# PhatStats_Slim_Enclosure_ESP_Lolin32_LIT.net
KiCad netlist of a schematic drawn in EAGLE
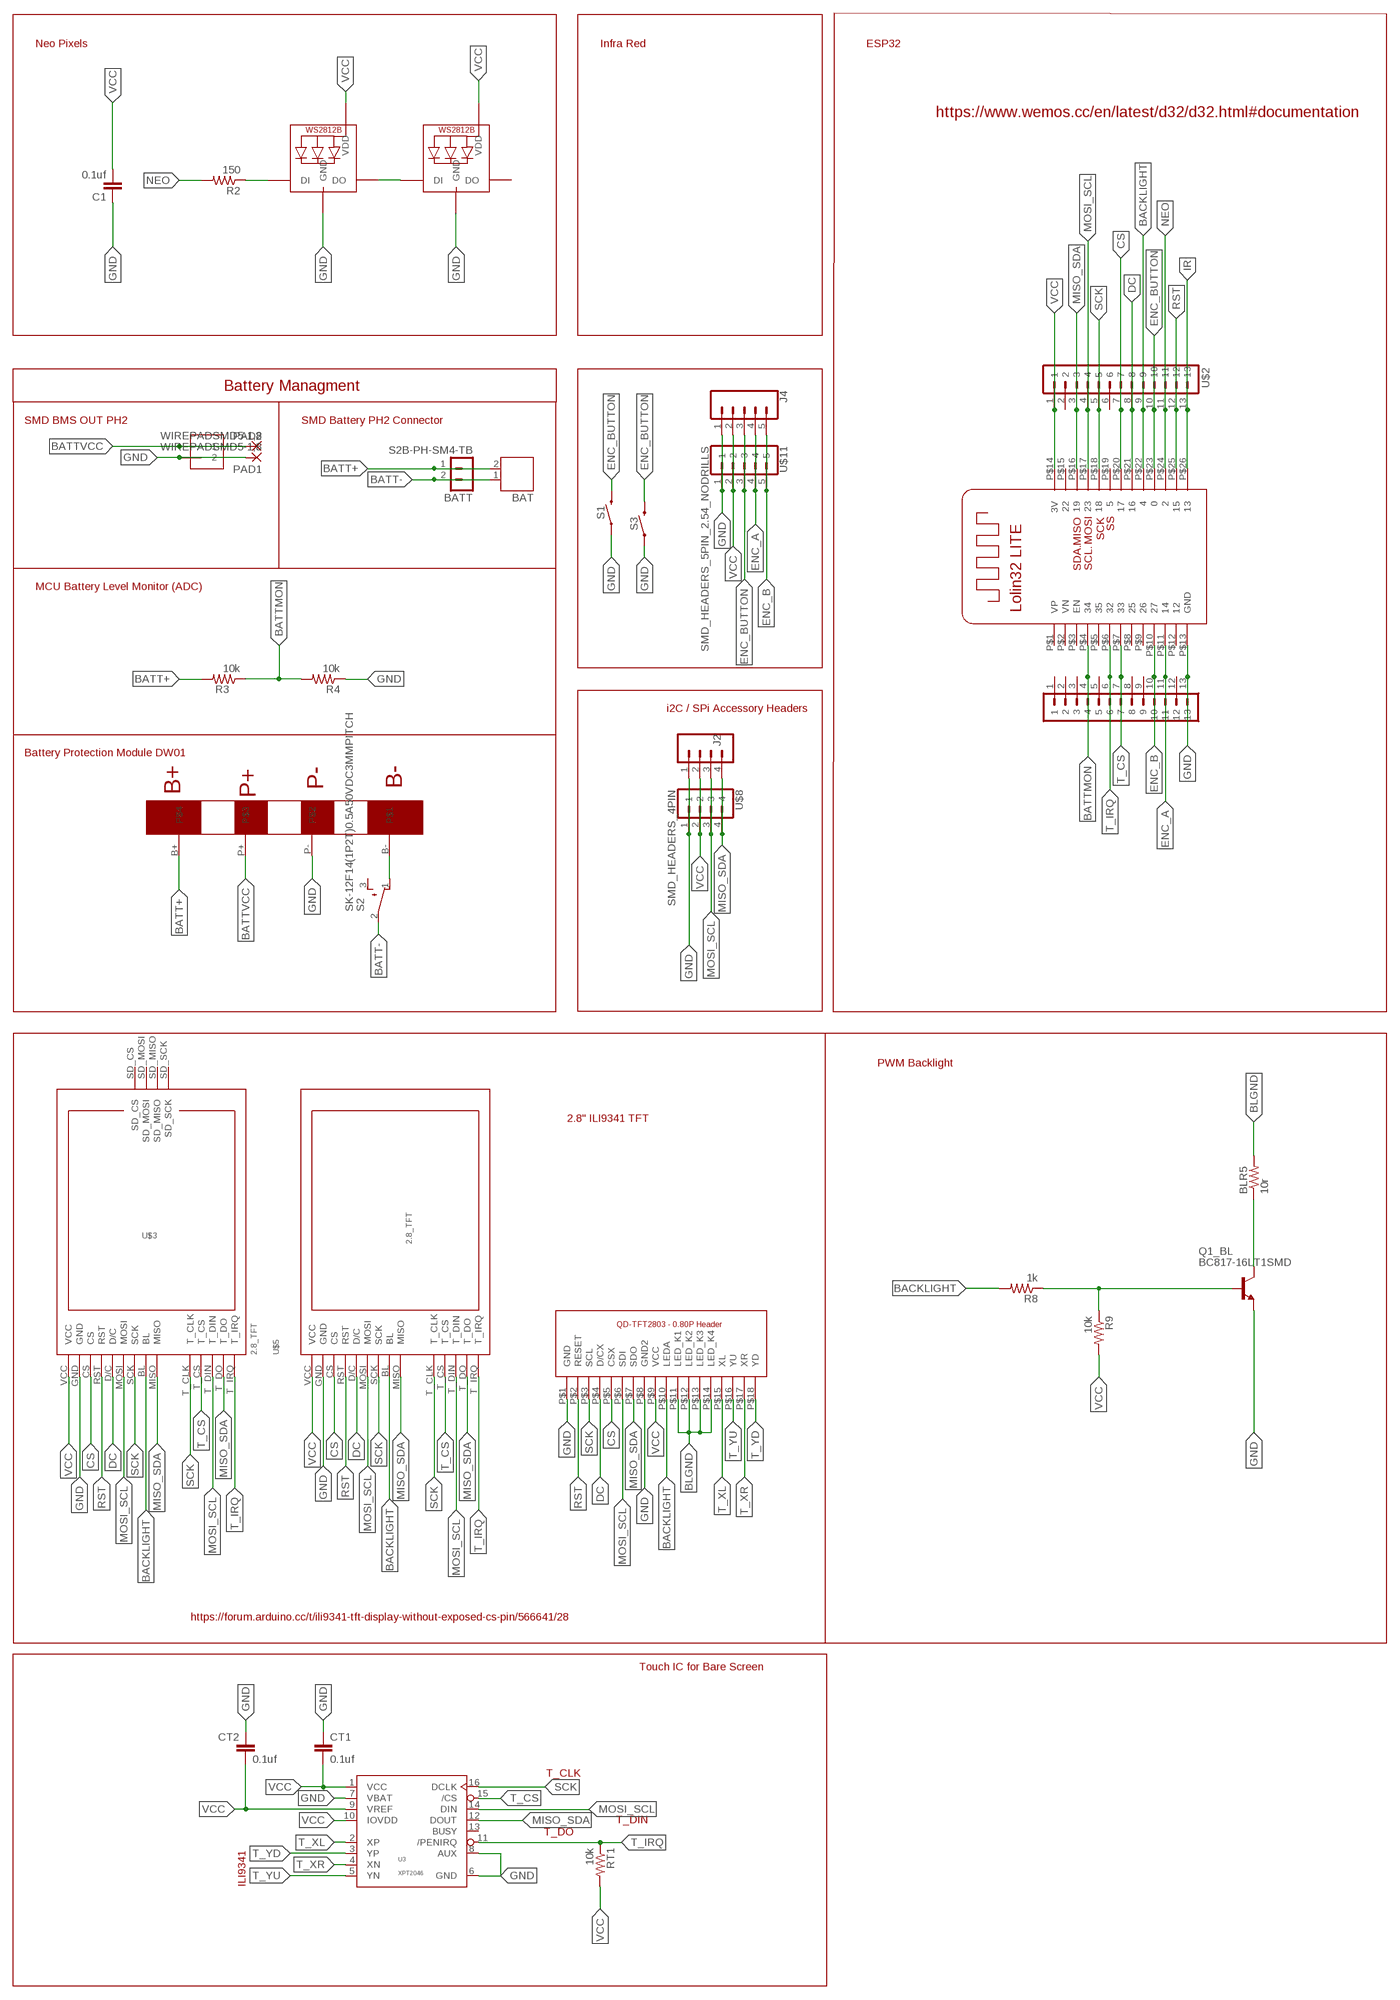
[diagram p0: schematic, sheet 1]

(export (version "E")
  (design (tool "Eeschema 10.0.6"))
  (components
    (comp (ref "0")
      (value "ILI9341-2.8")
      (footprint "eagle-import:ILI9341-2.8")
      (libsource (lib "eagle-import") (part "ILI9341-2.8"))
    )
    (comp (ref "BAT")
      (value "JST-PH2")
      (footprint "eagle-import:JST-PH2")
      (libsource (lib "eagle-import") (part "JST-PH2"))
    )
    (comp (ref "BATT")
      (value "S2B-PH-SM4-TB")
      (footprint "eagle-import:S2B-PH-SM4-TB")
      (libsource (lib "eagle-import") (part "S2B-PH-SM4-TB"))
    )
    (comp (ref "BLR5")
      (value "10r")
      (footprint "eagle-import:M1206")
      (libsource (lib "eagle-import") (part "R-US_M1206"))
    )
    (comp (ref "C1")
      (value "0.1uf")
      (footprint "eagle-import:C1206")
      (libsource (lib "eagle-import") (part "C-EUC1206"))
    )
    (comp (ref "CT1")
      (value "0.1uf")
      (footprint "eagle-import:C1206")
      (libsource (lib "eagle-import") (part "C-EUC1206"))
    )
    (comp (ref "CT2")
      (value "0.1uf")
      (footprint "eagle-import:C1206")
      (libsource (lib "eagle-import") (part "C-EUC1206"))
    )
    (comp (ref "DW01-BMS")
      (value "DW01BATTERYPROT")
      (footprint "eagle-import:DW01BATTERYPROT")
      (libsource (lib "eagle-import") (part "DW01BATTERYPROT"))
    )
    (comp (ref "J1")
      (value "1X2-3.5MM")
      (footprint "eagle-import:1X2-3.5MM")
      (libsource (lib "eagle-import") (part "1X2-3.5MM"))
    )
    (comp (ref "J2")
      (value "CONN_04PTH")
      (footprint "eagle-import:1X04")
      (libsource (lib "eagle-import") (part "CONN_04PTH"))
    )
    (comp (ref "J4")
      (value "CONN_05")
      (footprint "eagle-import:1X05")
      (libsource (lib "eagle-import") (part "CONN_05"))
    )
    (comp (ref "NEO1")
      (value "WS2812B5050")
      (footprint "eagle-import:WS2812B")
      (libsource (lib "eagle-import") (part "WS2812B5050"))
    )
    (comp (ref "NEO2")
      (value "WS2812B5050")
      (footprint "eagle-import:WS2812B")
      (libsource (lib "eagle-import") (part "WS2812B5050"))
    )
    (comp (ref "PAD1")
      (value "WIREPADSMD5-1,8")
      (footprint "eagle-import:5-1,8")
      (libsource (lib "eagle-import") (part "WIREPADSMD5-1,8"))
    )
    (comp (ref "PAD2")
      (value "WIREPADSMD5-1,8")
      (footprint "eagle-import:5-1,8")
      (libsource (lib "eagle-import") (part "WIREPADSMD5-1,8"))
    )
    (comp (ref "Q1_BL")
      (value "BC817-16LT1SMD")
      (footprint "eagle-import:SOT23-BEC")
      (libsource (lib "eagle-import") (part "BC817SMD-16LT1"))
    )
    (comp (ref "R2")
      (value "150")
      (footprint "eagle-import:M1206")
      (libsource (lib "eagle-import") (part "R-US_M1206"))
    )
    (comp (ref "R3")
      (value "10k")
      (footprint "eagle-import:M1206")
      (libsource (lib "eagle-import") (part "R-US_M1206"))
    )
    (comp (ref "R4")
      (value "10k")
      (footprint "eagle-import:M1206")
      (libsource (lib "eagle-import") (part "R-US_M1206"))
    )
    (comp (ref "R8")
      (value "1k")
      (footprint "eagle-import:M1206")
      (libsource (lib "eagle-import") (part "R-US_M1206"))
    )
    (comp (ref "R9")
      (value "10k")
      (footprint "eagle-import:M1206")
      (libsource (lib "eagle-import") (part "R-US_M1206"))
    )
    (comp (ref "RT1")
      (value "10k")
      (footprint "eagle-import:M1206")
      (libsource (lib "eagle-import") (part "R-US_M1206"))
    )
    (comp (ref "S1")
      (value "MOMENTARY-SWITCH-SPST-PTH-6.0MM")
      (footprint "eagle-import:TACTILE_SWITCH_PTH_6.0MM")
      (libsource (lib "eagle-import") (part "MOMENTARY-SWITCH-SPST-PTH-6.0MM"))
    )
    (comp (ref "S2")
      (value "SK-12F14(1P2T)0.5A50VDC3MMPITCH")
      (footprint "eagle-import:SK-12F14(1P2T)0.5A50VDC3MMPITCH")
      (libsource (lib "eagle-import") (part "SK-12F14(1P2T)0.5A50VDC3MMPITCH"))
    )
    (comp (ref "S3")
      (value "MOMENTARY-SWITCH-SPST-SMD-6.2MM-TALL")
      (footprint "eagle-import:TACTILE_SWITCH_SMD_6.2MM_TALL")
      (libsource (lib "eagle-import") (part "MOMENTARY-SWITCH-SPST-SMD-6.2MM-TALL"))
    )
    (comp (ref "U$1")
      (value "SMD_HEADERS_13PIN_2.54_NODRILLS")
      (footprint "eagle-import:SMD_HEADERS_13PIN")
      (libsource (lib "eagle-import") (part "SMD_HEADERS_13PIN_2.54_NODRILLS"))
    )
    (comp (ref "U$2")
      (value "SMD_HEADERS_13PIN_2.54_NODRILLS")
      (footprint "eagle-import:SMD_HEADERS_13PIN")
      (libsource (lib "eagle-import") (part "SMD_HEADERS_13PIN_2.54_NODRILLS"))
    )
    (comp (ref "U$3")
      (value "2.8_TFT")
      (footprint "eagle-import:2.8_TFT")
      (libsource (lib "eagle-import") (part "2.8_TFT"))
    )
    (comp (ref "U$5")
      (value "2.8_TFT")
      (footprint "eagle-import:2.8_TFT")
      (libsource (lib "eagle-import") (part "TML_ili9341-2.8_tft-display_PinHeader only_2.8_TFT"))
    )
    (comp (ref "U$7")
      (value "TML_LOLIND32_LITE")
      (footprint "eagle-import:TML_LOLIND32_LITE")
      (libsource (lib "eagle-import") (part "TML_LOLIND32_LITE"))
    )
    (comp (ref "U$8")
      (value "SMD_HEADERS_4PIN")
      (footprint "eagle-import:SMD_HEADERS_4PIN")
      (libsource (lib "eagle-import") (part "SMD_HEADERS_4PIN"))
    )
    (comp (ref "U$11")
      (value "SMD_HEADERS_5PIN_2.54_NODRILLS")
      (footprint "eagle-import:SMD_HEADERS_5PIN")
      (libsource (lib "eagle-import") (part "SMD_HEADERS_5PIN_2.54_NODRILLS"))
    )
    (comp (ref "U3")
      (value "XPT2046")
      (footprint "eagle-import:TSSOP-16")
      (fields (field (name "MF") "Xptek"))
      (libsource (lib "eagle-import") (part "XPT2046"))
    )
  )
  (nets
    (net (code "1") (name "BACKLIGHT") (class "Default")
      (node (ref "0") (pin "P$10") (pinfunction "LEDA_P$10") (pintype "bidirectional"))
      (node (ref "R8") (pin "2") (pinfunction "2_2") (pintype "passive"))
      (node (ref "U$2") (pin "9") (pinfunction "9_9") (pintype "bidirectional"))
      (node (ref "U$3") (pin "BL") (pinfunction "BL_BL") (pintype "bidirectional"))
      (node (ref "U$5") (pin "BL") (pinfunction "BL_BL") (pintype "bidirectional"))
      (node (ref "U$7") (pin "P$22") (pinfunction "4_P$22") (pintype "bidirectional"))
    )
    (net (code "2") (name "BATT+") (class "Default")
      (node (ref "BAT") (pin "2") (pinfunction "2_2") (pintype "passive"))
      (node (ref "BATT") (pin "1") (pinfunction "1_1") (pintype "passive"))
      (node (ref "DW01-BMS") (pin "B+") (pinfunction "P$4_B+") (pintype "bidirectional"))
      (node (ref "R3") (pin "2") (pinfunction "2_2") (pintype "passive"))
    )
    (net (code "3") (name "BATT-") (class "Default")
      (node (ref "BAT") (pin "1") (pinfunction "1_1") (pintype "passive"))
      (node (ref "BATT") (pin "2") (pinfunction "2_2") (pintype "passive"))
      (node (ref "S2") (pin "2") (pinfunction "P_2") (pintype "passive"))
    )
    (net (code "4") (name "BATTMON") (class "Default")
      (node (ref "R3") (pin "1") (pinfunction "1_1") (pintype "passive"))
      (node (ref "R4") (pin "2") (pinfunction "2_2") (pintype "passive"))
      (node (ref "U$1") (pin "4") (pinfunction "4_4") (pintype "bidirectional"))
      (node (ref "U$7") (pin "P$4") (pinfunction "34_P$4") (pintype "bidirectional"))
    )
    (net (code "5") (name "BATTVCC") (class "Default")
      (node (ref "DW01-BMS") (pin "P+") (pinfunction "P$3_P+") (pintype "bidirectional"))
      (node (ref "J1") (pin "1") (pinfunction "1_1") (pintype "passive"))
      (node (ref "PAD2") (pin "1") (pinfunction "P_1") (pintype "passive"))
    )
    (net (code "6") (name "BLGND") (class "Default")
      (node (ref "0") (pin "P$11") (pinfunction "LED_K1_P$11") (pintype "bidirectional"))
      (node (ref "0") (pin "P$12") (pinfunction "LED_K2_P$12") (pintype "bidirectional"))
      (node (ref "0") (pin "P$13") (pinfunction "LED_K3_P$13") (pintype "bidirectional"))
      (node (ref "0") (pin "P$14") (pinfunction "LED_K4_P$14") (pintype "bidirectional"))
      (node (ref "BLR5") (pin "2") (pinfunction "2_2") (pintype "passive"))
    )
    (net (code "7") (name "CS") (class "Default")
      (node (ref "0") (pin "P$5") (pinfunction "CSX_P$5") (pintype "bidirectional"))
      (node (ref "U$2") (pin "7") (pinfunction "7_7") (pintype "bidirectional"))
      (node (ref "U$3") (pin "CS") (pinfunction "CS_CS") (pintype "bidirectional"))
      (node (ref "U$5") (pin "CS") (pinfunction "CS_CS") (pintype "bidirectional"))
      (node (ref "U$7") (pin "P$20") (pinfunction "17_P$20") (pintype "bidirectional"))
    )
    (net (code "8") (name "DC") (class "Default")
      (node (ref "0") (pin "P$4") (pinfunction "D/CX_P$4") (pintype "bidirectional"))
      (node (ref "U$2") (pin "8") (pinfunction "8_8") (pintype "bidirectional"))
      (node (ref "U$3") (pin "D/C") (pinfunction "D/C_D/C") (pintype "bidirectional"))
      (node (ref "U$5") (pin "D/C") (pinfunction "D/C_D/C") (pintype "bidirectional"))
      (node (ref "U$7") (pin "P$21") (pinfunction "16_P$21") (pintype "bidirectional"))
    )
    (net (code "9") (name "ENC_A") (class "Default")
      (node (ref "J4") (pin "4") (pinfunction "4_4") (pintype "passive"))
      (node (ref "U$1") (pin "11") (pinfunction "11_11") (pintype "bidirectional"))
      (node (ref "U$11") (pin "4") (pinfunction "4_4") (pintype "passive"))
      (node (ref "U$7") (pin "P$11") (pinfunction "14_P$11") (pintype "bidirectional"))
    )
    (net (code "10") (name "ENC_B") (class "Default")
      (node (ref "J4") (pin "5") (pinfunction "5_5") (pintype "passive"))
      (node (ref "U$1") (pin "10") (pinfunction "10_10") (pintype "bidirectional"))
      (node (ref "U$11") (pin "5") (pinfunction "5_5") (pintype "passive"))
      (node (ref "U$7") (pin "P$10") (pinfunction "27_P$10") (pintype "bidirectional"))
    )
    (net (code "11") (name "ENC_BUTTON") (class "Default")
      (node (ref "J4") (pin "3") (pinfunction "3_3") (pintype "passive"))
      (node (ref "S1") (pin "3") (pinfunction "2_3") (pintype "passive"))
      (node (ref "S3") (pin "B2") (pinfunction "2_B2") (pintype "passive"))
      (node (ref "U$11") (pin "3") (pinfunction "3_3") (pintype "passive"))
      (node (ref "U$2") (pin "10") (pinfunction "10_10") (pintype "bidirectional"))
      (node (ref "U$7") (pin "P$23") (pinfunction "0_P$23") (pintype "bidirectional"))
    )
    (net (code "12") (name "GND") (class "Default")
      (node (ref "0") (pin "P$1") (pinfunction "GND_P$1") (pintype "bidirectional"))
      (node (ref "0") (pin "P$8") (pinfunction "GND2_P$8") (pintype "bidirectional"))
      (node (ref "C1") (pin "1") (pinfunction "1_1") (pintype "passive"))
      (node (ref "CT1") (pin "1") (pinfunction "1_1") (pintype "passive"))
      (node (ref "CT2") (pin "1") (pinfunction "1_1") (pintype "passive"))
      (node (ref "DW01-BMS") (pin "P-") (pinfunction "P$2_P-") (pintype "bidirectional"))
      (node (ref "J1") (pin "2") (pinfunction "2_2") (pintype "passive"))
      (node (ref "J2") (pin "1") (pinfunction "1_1") (pintype "passive"))
      (node (ref "J4") (pin "1") (pinfunction "1_1") (pintype "passive"))
      (node (ref "NEO1") (pin "3-GND") (pinfunction "GND_3-GND") (pintype "power_in"))
      (node (ref "NEO2") (pin "3-GND") (pinfunction "GND_3-GND") (pintype "power_in"))
      (node (ref "PAD1") (pin "1") (pinfunction "P_1") (pintype "passive"))
      (node (ref "Q1_BL") (pin "E") (pinfunction "E_E") (pintype "passive"))
      (node (ref "R4") (pin "1") (pinfunction "1_1") (pintype "passive"))
      (node (ref "S1") (pin "1") (pinfunction "1_1") (pintype "passive"))
      (node (ref "S3") (pin "A2") (pinfunction "1_A2") (pintype "passive"))
      (node (ref "U$1") (pin "13") (pinfunction "13_13") (pintype "bidirectional"))
      (node (ref "U$11") (pin "1") (pinfunction "1_1") (pintype "passive"))
      (node (ref "U$3") (pin "GND") (pinfunction "GND_GND") (pintype "bidirectional"))
      (node (ref "U$5") (pin "GND") (pinfunction "GND_GND") (pintype "bidirectional"))
      (node (ref "U$7") (pin "P$13") (pinfunction "GND_P$13") (pintype "input"))
      (node (ref "U$8") (pin "1") (pinfunction "1_1") (pintype "passive"))
      (node (ref "U3") (pin "6") (pinfunction "GND_6") (pintype "power_in"))
      (node (ref "U3") (pin "7") (pinfunction "VBAT_7") (pintype "input"))
      (node (ref "U3") (pin "8") (pinfunction "AUX_8") (pintype "input"))
    )
    (net (code "13") (name "IR") (class "Default")
      (node (ref "U$2") (pin "13") (pinfunction "13_13") (pintype "bidirectional"))
      (node (ref "U$7") (pin "P$26") (pinfunction "13_P$26") (pintype "bidirectional"))
    )
    (net (code "14") (name "MISO_SDA") (class "Default")
      (node (ref "0") (pin "P$7") (pinfunction "SDO_P$7") (pintype "bidirectional"))
      (node (ref "J2") (pin "4") (pinfunction "4_4") (pintype "passive"))
      (node (ref "U$2") (pin "3") (pinfunction "3_3") (pintype "bidirectional"))
      (node (ref "U$3") (pin "MISO") (pinfunction "MISO_MISO") (pintype "bidirectional"))
      (node (ref "U$3") (pin "T_DO") (pinfunction "T_DO_T_DO") (pintype "bidirectional"))
      (node (ref "U$5") (pin "MISO") (pinfunction "MISO_MISO") (pintype "bidirectional"))
      (node (ref "U$5") (pin "T_DO") (pinfunction "T_DO_T_DO") (pintype "bidirectional"))
      (node (ref "U$7") (pin "P$16") (pinfunction "19_P$16") (pintype "bidirectional"))
      (node (ref "U$8") (pin "4") (pinfunction "4_4") (pintype "passive"))
      (node (ref "U3") (pin "12") (pinfunction "DOUT_12") (pintype "output"))
    )
    (net (code "15") (name "MOSI_SCL") (class "Default")
      (node (ref "0") (pin "P$6") (pinfunction "SDI_P$6") (pintype "bidirectional"))
      (node (ref "J2") (pin "3") (pinfunction "3_3") (pintype "passive"))
      (node (ref "U$2") (pin "4") (pinfunction "4_4") (pintype "bidirectional"))
      (node (ref "U$3") (pin "MOSI") (pinfunction "MOSI_MOSI") (pintype "bidirectional"))
      (node (ref "U$3") (pin "T_DIN") (pinfunction "T_DIN_T_DIN") (pintype "bidirectional"))
      (node (ref "U$5") (pin "MOSI") (pinfunction "MOSI_MOSI") (pintype "bidirectional"))
      (node (ref "U$5") (pin "T_DIN") (pinfunction "T_DIN_T_DIN") (pintype "bidirectional"))
      (node (ref "U$7") (pin "P$17") (pinfunction "23_P$17") (pintype "bidirectional"))
      (node (ref "U$8") (pin "3") (pinfunction "3_3") (pintype "passive"))
      (node (ref "U3") (pin "14") (pinfunction "DIN_14") (pintype "input"))
    )
    (net (code "16") (name "NEO") (class "Default")
      (node (ref "R2") (pin "2") (pinfunction "2_2") (pintype "passive"))
      (node (ref "U$2") (pin "11") (pinfunction "11_11") (pintype "bidirectional"))
      (node (ref "U$7") (pin "P$24") (pinfunction "2_P$24") (pintype "bidirectional"))
    )
    (net (code "17") (name "Net-(BLR5-Pad1)") (class "Default")
      (node (ref "BLR5") (pin "1") (pinfunction "1_1") (pintype "passive"))
      (node (ref "Q1_BL") (pin "C") (pinfunction "C_C") (pintype "passive"))
    )
    (net (code "18") (name "Net-(DW01-BMS-P$1)") (class "Default")
      (node (ref "DW01-BMS") (pin "B-") (pinfunction "P$1_B-") (pintype "bidirectional"))
      (node (ref "S2") (pin "1") (pinfunction "O_1") (pintype "passive"))
    )
    (net (code "19") (name "Net-(NEO1-DI)") (class "Default")
      (node (ref "NEO1") (pin "4-DIN") (pinfunction "DI_4-DIN") (pintype "input"))
      (node (ref "R2") (pin "1") (pinfunction "1_1") (pintype "passive"))
    )
    (net (code "20") (name "Net-(NEO1-DO)") (class "Default")
      (node (ref "NEO1") (pin "2-DOUT") (pinfunction "DO_2-DOUT") (pintype "output"))
      (node (ref "NEO2") (pin "4-DIN") (pinfunction "DI_4-DIN") (pintype "input"))
    )
    (net (code "21") (name "Net-(Q1_BL-PadB)") (class "Default")
      (node (ref "Q1_BL") (pin "B") (pinfunction "B_B") (pintype "passive"))
      (node (ref "R8") (pin "1") (pinfunction "1_1") (pintype "passive"))
      (node (ref "R9") (pin "1") (pinfunction "1_1") (pintype "passive"))
    )
    (net (code "22") (name "RST") (class "Default")
      (node (ref "0") (pin "P$2") (pinfunction "RESET_P$2") (pintype "bidirectional"))
      (node (ref "U$2") (pin "12") (pinfunction "12_12") (pintype "bidirectional"))
      (node (ref "U$3") (pin "RST") (pinfunction "RST_RST") (pintype "bidirectional"))
      (node (ref "U$5") (pin "RST") (pinfunction "RST_RST") (pintype "bidirectional"))
      (node (ref "U$7") (pin "P$25") (pinfunction "15_P$25") (pintype "bidirectional"))
    )
    (net (code "23") (name "SCK") (class "Default")
      (node (ref "0") (pin "P$3") (pinfunction "SCL_P$3") (pintype "bidirectional"))
      (node (ref "U$2") (pin "5") (pinfunction "5_5") (pintype "bidirectional"))
      (node (ref "U$3") (pin "SCK") (pinfunction "SCK_SCK") (pintype "bidirectional"))
      (node (ref "U$3") (pin "T_CLK") (pinfunction "T_CLK_T_CLK") (pintype "bidirectional"))
      (node (ref "U$5") (pin "SCK") (pinfunction "SCK_SCK") (pintype "bidirectional"))
      (node (ref "U$5") (pin "T_CLK") (pinfunction "T_CLK_T_CLK") (pintype "bidirectional"))
      (node (ref "U$7") (pin "P$18") (pinfunction "18_P$18") (pintype "bidirectional"))
      (node (ref "U3") (pin "16") (pinfunction "DCLK_16") (pintype "input"))
    )
    (net (code "24") (name "T_CS") (class "Default")
      (node (ref "U$1") (pin "7") (pinfunction "7_7") (pintype "bidirectional"))
      (node (ref "U$3") (pin "T_CS") (pinfunction "T_CS_T_CS") (pintype "bidirectional"))
      (node (ref "U$5") (pin "T_CS") (pinfunction "T_CS_T_CS") (pintype "bidirectional"))
      (node (ref "U$7") (pin "P$7") (pinfunction "33_P$7") (pintype "bidirectional"))
      (node (ref "U3") (pin "15") (pinfunction "/CS_15") (pintype "input"))
    )
    (net (code "25") (name "T_IRQ") (class "Default")
      (node (ref "RT1") (pin "1") (pinfunction "1_1") (pintype "passive"))
      (node (ref "U$1") (pin "6") (pinfunction "6_6") (pintype "bidirectional"))
      (node (ref "U$3") (pin "T_IRQ") (pinfunction "T_IRQ_T_IRQ") (pintype "bidirectional"))
      (node (ref "U$5") (pin "T_IRQ") (pinfunction "T_IRQ_T_IRQ") (pintype "bidirectional"))
      (node (ref "U$7") (pin "P$6") (pinfunction "32_P$6") (pintype "bidirectional"))
      (node (ref "U3") (pin "11") (pinfunction "/PENIRQ_11") (pintype "output"))
    )
    (net (code "26") (name "T_XL") (class "Default")
      (node (ref "0") (pin "P$15") (pinfunction "XL_P$15") (pintype "bidirectional"))
      (node (ref "U3") (pin "2") (pinfunction "XP_2") (pintype "input"))
    )
    (net (code "27") (name "T_XR") (class "Default")
      (node (ref "0") (pin "P$17") (pinfunction "XR_P$17") (pintype "bidirectional"))
      (node (ref "U3") (pin "4") (pinfunction "XN_4") (pintype "input"))
    )
    (net (code "28") (name "T_YD") (class "Default")
      (node (ref "0") (pin "P$18") (pinfunction "YD_P$18") (pintype "bidirectional"))
      (node (ref "U3") (pin "3") (pinfunction "YP_3") (pintype "input"))
    )
    (net (code "29") (name "T_YU") (class "Default")
      (node (ref "0") (pin "P$16") (pinfunction "YU_P$16") (pintype "bidirectional"))
      (node (ref "U3") (pin "5") (pinfunction "YN_5") (pintype "input"))
    )
    (net (code "30") (name "VCC") (class "Default")
      (node (ref "0") (pin "P$9") (pinfunction "VCC_P$9") (pintype "bidirectional"))
      (node (ref "C1") (pin "2") (pinfunction "2_2") (pintype "passive"))
      (node (ref "CT1") (pin "2") (pinfunction "2_2") (pintype "passive"))
      (node (ref "CT2") (pin "2") (pinfunction "2_2") (pintype "passive"))
      (node (ref "J2") (pin "2") (pinfunction "2_2") (pintype "passive"))
      (node (ref "J4") (pin "2") (pinfunction "2_2") (pintype "passive"))
      (node (ref "NEO1") (pin "1-VDD") (pinfunction "VDD_1-VDD") (pintype "power_in"))
      (node (ref "NEO2") (pin "1-VDD") (pinfunction "VDD_1-VDD") (pintype "power_in"))
      (node (ref "R9") (pin "2") (pinfunction "2_2") (pintype "passive"))
      (node (ref "RT1") (pin "2") (pinfunction "2_2") (pintype "passive"))
      (node (ref "U$11") (pin "2") (pinfunction "2_2") (pintype "passive"))
      (node (ref "U$2") (pin "1") (pinfunction "1_1") (pintype "bidirectional"))
      (node (ref "U$3") (pin "VCC") (pinfunction "VCC_VCC") (pintype "bidirectional"))
      (node (ref "U$5") (pin "VCC") (pinfunction "VCC_VCC") (pintype "bidirectional"))
      (node (ref "U$7") (pin "P$14") (pinfunction "3V_P$14") (pintype "input"))
      (node (ref "U$8") (pin "2") (pinfunction "2_2") (pintype "passive"))
      (node (ref "U3") (pin "1") (pinfunction "VCC_1") (pintype "power_in"))
      (node (ref "U3") (pin "10") (pinfunction "IOVDD_10") (pintype "power_in"))
      (node (ref "U3") (pin "9") (pinfunction "VREF_9") (pintype "input"))
    )
    (net (code "31") (name "unconnected-(NEO2-DO-Pad2-DOUT)") (class "Default")
      (node (ref "NEO2") (pin "2-DOUT") (pinfunction "DO_2-DOUT") (pintype "output"))
    )
    (net (code "32") (name "unconnected-(S2-S-Pad3)") (class "Default")
      (node (ref "S2") (pin "3") (pinfunction "S_3") (pintype "passive"))
    )
    (net (code "33") (name "unconnected-(U$1-Pad1)") (class "Default")
      (node (ref "U$1") (pin "1") (pinfunction "1_1") (pintype "bidirectional"))
    )
    (net (code "34") (name "unconnected-(U$1-Pad2)") (class "Default")
      (node (ref "U$1") (pin "2") (pinfunction "2_2") (pintype "bidirectional"))
    )
    (net (code "35") (name "unconnected-(U$1-Pad3)") (class "Default")
      (node (ref "U$1") (pin "3") (pinfunction "3_3") (pintype "bidirectional"))
    )
    (net (code "36") (name "unconnected-(U$1-Pad5)") (class "Default")
      (node (ref "U$1") (pin "5") (pinfunction "5_5") (pintype "bidirectional"))
    )
    (net (code "37") (name "unconnected-(U$1-Pad8)") (class "Default")
      (node (ref "U$1") (pin "8") (pinfunction "8_8") (pintype "bidirectional"))
    )
    (net (code "38") (name "unconnected-(U$1-Pad9)") (class "Default")
      (node (ref "U$1") (pin "9") (pinfunction "9_9") (pintype "bidirectional"))
    )
    (net (code "39") (name "unconnected-(U$1-Pad12)") (class "Default")
      (node (ref "U$1") (pin "12") (pinfunction "12_12") (pintype "bidirectional"))
    )
    (net (code "40") (name "unconnected-(U$2-Pad2)") (class "Default")
      (node (ref "U$2") (pin "2") (pinfunction "2_2") (pintype "bidirectional"))
    )
    (net (code "41") (name "unconnected-(U$2-Pad6)") (class "Default")
      (node (ref "U$2") (pin "6") (pinfunction "6_6") (pintype "bidirectional"))
    )
    (net (code "42") (name "unconnected-(U$3-PadSD_CS)") (class "Default")
      (node (ref "U$3") (pin "SD_CS") (pinfunction "SD_CS_SD_CS") (pintype "bidirectional"))
    )
    (net (code "43") (name "unconnected-(U$3-PadSD_MISO)") (class "Default")
      (node (ref "U$3") (pin "SD_MISO") (pinfunction "SD_MISO_SD_MISO") (pintype "bidirectional"))
    )
    (net (code "44") (name "unconnected-(U$3-PadSD_MOSI)") (class "Default")
      (node (ref "U$3") (pin "SD_MOSI") (pinfunction "SD_MOSI_SD_MOSI") (pintype "bidirectional"))
    )
    (net (code "45") (name "unconnected-(U$3-PadSD_SCK)") (class "Default")
      (node (ref "U$3") (pin "SD_SCK") (pinfunction "SD_SCK_SD_SCK") (pintype "bidirectional"))
    )
    (net (code "46") (name "unconnected-(U$7-5-PadP$19)") (class "Default")
      (node (ref "U$7") (pin "P$19") (pinfunction "5_P$19") (pintype "bidirectional"))
    )
    (net (code "47") (name "unconnected-(U$7-12-PadP$12)") (class "Default")
      (node (ref "U$7") (pin "P$12") (pinfunction "12_P$12") (pintype "bidirectional"))
    )
    (net (code "48") (name "unconnected-(U$7-22-PadP$15)") (class "Default")
      (node (ref "U$7") (pin "P$15") (pinfunction "22_P$15") (pintype "bidirectional"))
    )
    (net (code "49") (name "unconnected-(U$7-25-PadP$8)") (class "Default")
      (node (ref "U$7") (pin "P$8") (pinfunction "25_P$8") (pintype "bidirectional"))
    )
    (net (code "50") (name "unconnected-(U$7-26-PadP$9)") (class "Default")
      (node (ref "U$7") (pin "P$9") (pinfunction "26_P$9") (pintype "bidirectional"))
    )
    (net (code "51") (name "unconnected-(U$7-35-PadP$5)") (class "Default")
      (node (ref "U$7") (pin "P$5") (pinfunction "35_P$5") (pintype "bidirectional"))
    )
    (net (code "52") (name "unconnected-(U$7-EN-PadP$3)") (class "Default")
      (node (ref "U$7") (pin "P$3") (pinfunction "EN_P$3") (pintype "bidirectional"))
    )
    (net (code "53") (name "unconnected-(U$7-VN-PadP$2)") (class "Default")
      (node (ref "U$7") (pin "P$2") (pinfunction "VN_P$2") (pintype "bidirectional"))
    )
    (net (code "54") (name "unconnected-(U$7-VP-PadP$1)") (class "Default")
      (node (ref "U$7") (pin "P$1") (pinfunction "VP_P$1") (pintype "bidirectional"))
    )
    (net (code "55") (name "unconnected-(U3-BUSY-Pad13)") (class "Default")
      (node (ref "U3") (pin "13") (pinfunction "BUSY_13") (pintype "output"))
    )
  )
)
